# MCU_Signals.net
KiCad netlist of a schematic drawn in Altium Designer
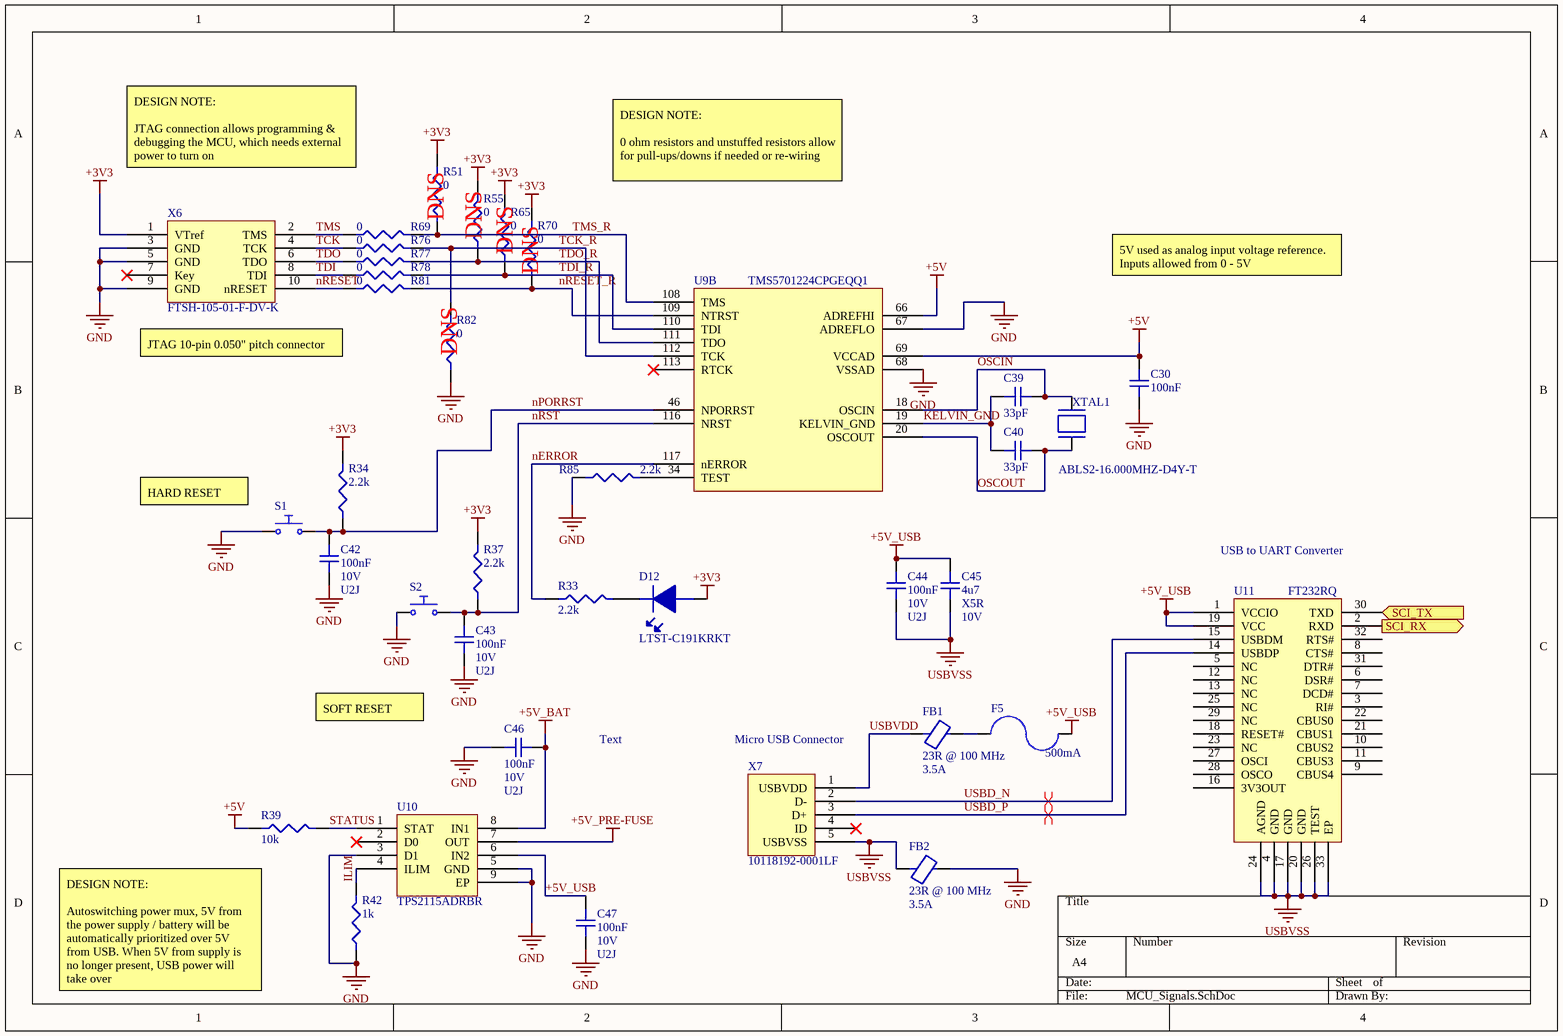
[diagram p0: MCU_Signals.SchDoc]

(export (version "E")
  (design (tool "Eeschema 10.0.6"))
  (components
    (comp (ref "C30")
      (value "100nF")
      (footprint "PHANTOM_FOOTPRINTS:C0805")
      (description "CAP MLCC 100nF 10Volts U2J 5%")
      (fields
        (field (name "MANUFACTURER") "Murata")
        (field (name "MANUFACTURER PART NUMBER") "GRM21B7U1A104JA01L")
      )
      (libsource (lib "PHANTOM_LIBRARY") (part "GRM21B7U1A104JA01L"))
    )
    (comp (ref "C39")
      (value "33pF")
      (footprint "C0805")
      (fields
        (field (name "MANUFACTURER") "Wurth Electronics")
        (field (name "MANUFACTURER PART NUMBER") "885012007003")
        (field (name "TOLERANCE") "5%")
      )
      (libsource (lib "PHANTOM_LIBRARY") (part "885012007003"))
    )
    (comp (ref "C40")
      (value "33pF")
      (footprint "C0805")
      (fields
        (field (name "MANUFACTURER") "Wurth Electronics")
        (field (name "MANUFACTURER PART NUMBER") "885012007003")
        (field (name "TOLERANCE") "5%")
      )
      (libsource (lib "PHANTOM_LIBRARY") (part "885012007003"))
    )
    (comp (ref "C42")
      (value "100nF")
      (footprint "PHANTOM_FOOTPRINTS:C0805")
      (description "CAP MLCC 100nF 10Volts U2J 5%")
      (fields
        (field (name "MANUFACTURER") "Murata")
        (field (name "MANUFACTURER PART NUMBER") "GRM21B7U1A104JA01L")
        (field (name "VOLTAGE RATING") "10V")
        (field (name "DIELECTRIC") "U2J")
      )
      (libsource (lib "PHANTOM_LIBRARY") (part "GRM21B7U1A104JA01L"))
    )
    (comp (ref "C43")
      (value "100nF")
      (footprint "PHANTOM_FOOTPRINTS:C0805")
      (description "CAP MLCC 100nF 10Volts U2J 5%")
      (fields
        (field (name "MANUFACTURER") "Murata")
        (field (name "MANUFACTURER PART NUMBER") "GRM21B7U1A104JA01L")
        (field (name "VOLTAGE RATING") "10V")
        (field (name "DIELECTRIC") "U2J")
      )
      (libsource (lib "PHANTOM_LIBRARY") (part "GRM21B7U1A104JA01L"))
    )
    (comp (ref "C44")
      (value "100nF")
      (footprint "PHANTOM_FOOTPRINTS:C0805")
      (description "CAP MLCC 100nF 10Volts U2J 5%")
      (fields
        (field (name "MANUFACTURER") "Murata")
        (field (name "MANUFACTURER PART NUMBER") "GRM21B7U1A104JA01L")
        (field (name "VOLTAGE RATING") "10V")
        (field (name "DIELECTRIC") "U2J")
      )
      (libsource (lib "PHANTOM_LIBRARY") (part "GRM21B7U1A104JA01L"))
    )
    (comp (ref "C45")
      (value "4u7")
      (footprint "C0805")
      (fields
        (field (name "MANUFACTURER") "Murata")
        (field (name "MANUFACTURER PART NUMBER") "GRM219R61A475KE34D")
        (field (name "TOLERANCE") "10%")
        (field (name "DIELECTRIC") "X5R")
        (field (name "VOLTAGE") "10V")
      )
      (libsource (lib "PHANTOM_LIBRARY") (part "GRM219R61A475KE34D"))
    )
    (comp (ref "C46")
      (value "100nF")
      (footprint "PHANTOM_FOOTPRINTS:C0805")
      (description "CAP MLCC 100nF 10Volts U2J 5%")
      (fields
        (field (name "MANUFACTURER") "Murata")
        (field (name "MANUFACTURER PART NUMBER") "GRM21B7U1A104JA01L")
        (field (name "VOLTAGE RATING") "10V")
        (field (name "DIELECTRIC") "U2J")
      )
      (libsource (lib "PHANTOM_LIBRARY") (part "GRM21B7U1A104JA01L"))
    )
    (comp (ref "C47")
      (value "100nF")
      (footprint "PHANTOM_FOOTPRINTS:C0805")
      (description "CAP MLCC 100nF 10Volts U2J 5%")
      (fields
        (field (name "MANUFACTURER") "Murata")
        (field (name "MANUFACTURER PART NUMBER") "GRM21B7U1A104JA01L")
        (field (name "VOLTAGE RATING") "10V")
        (field (name "DIELECTRIC") "U2J")
      )
      (libsource (lib "PHANTOM_LIBRARY") (part "GRM21B7U1A104JA01L"))
    )
    (comp (ref "D12")
      (value "LTST-C191KRKT")
      (footprint "LED_0603")
      (description "LED RED CLEAR 0603 SMD")
      (fields (field (name "MANUFACTURER") "Vishay Lite-On") (field (name "VOLTAGE") "2V"))
      (libsource (lib "PHANTOM_LIBRARY") (part "LTST-C191KRKT"))
    )
    (comp (ref "F5")
      (value "500mA")
      (footprint "FUSE_0603")
      (description "FUSE_0.5A SMD 0603, 0.5A")
      (fields
        (field (name "MANUFACTURER") "Panasonic ECG")
        (field (name "MANUFACTURER PART NUMBER") "ERB-RE0R50V")
      )
      (libsource (lib "PHANTOM_LIBRARY") (part "ERB-RE0R50V"))
    )
    (comp (ref "FB1")
      (value "23R @ 100 MHz")
      (footprint "FB_1806")
      (description "FERRITE BEAD Ind Chip Bead Multi-Layer 23Ohm 30% 100MHz Ferrite 3.5A 1806 T/R")
      (fields
        (field (name "MANUFACTURER") "Taiyo Yuden")
        (field (name "MANUFACTURER PART NUMBER") "FBMJ4516HL230NTV")
        (field (name "MAX CURRENT RATING") "3.5A")
      )
      (libsource (lib "PHANTOM_LIBRARY") (part "FBMJ4516HL230NTV"))
    )
    (comp (ref "FB2")
      (value "23R @ 100 MHz")
      (footprint "FB_1806")
      (description "FERRITE BEAD Ind Chip Bead Multi-Layer 23Ohm 30% 100MHz Ferrite 3.5A 1806 T/R")
      (fields
        (field (name "MANUFACTURER") "Taiyo Yuden")
        (field (name "MANUFACTURER PART NUMBER") "FBMJ4516HL230NTV")
        (field (name "MAX CURRENT RATING") "3.5A")
      )
      (libsource (lib "PHANTOM_LIBRARY") (part "FBMJ4516HL230NTV"))
    )
    (comp (ref "R33")
      (value "2.2k")
      (footprint "R0805")
      (description "RES SMD 2.2K OHM 5% 1/8W")
      (fields
        (field (name "MANUFACTURER") "Yageo")
        (field (name "MANUFACTURER PART NUMBER") "RC0805JR-072K2L")
      )
      (libsource (lib "PHANTOM_LIBRARY") (part "RC0805JR-072K2L"))
    )
    (comp (ref "R34")
      (value "2.2k")
      (footprint "R0805")
      (description "RES SMD 2.2K OHM 5% 1/8W")
      (fields
        (field (name "MANUFACTURER") "Yageo")
        (field (name "MANUFACTURER PART NUMBER") "RC0805JR-072K2L")
      )
      (libsource (lib "PHANTOM_LIBRARY") (part "RC0805JR-072K2L"))
    )
    (comp (ref "R37")
      (value "2.2k")
      (footprint "R0805")
      (description "RES SMD 2.2K OHM 5% 1/8W")
      (fields
        (field (name "MANUFACTURER") "Yageo")
        (field (name "MANUFACTURER PART NUMBER") "RC0805JR-072K2L")
      )
      (libsource (lib "PHANTOM_LIBRARY") (part "RC0805JR-072K2L"))
    )
    (comp (ref "R39")
      (value "10k")
      (footprint "R0805")
      (description "RES SMD 10K OHM 1% 1/8W 0805")
      (fields
        (field (name "MANUFACTURER") "Yageo Phycomp")
        (field (name "MANUFACTURER PART NUMBER") "RC0805FR-071KL")
      )
      (libsource (lib "PHANTOM_LIBRARY") (part "RC0805FR-071KL"))
    )
    (comp (ref "R42")
      (value "1k")
      (footprint "R0805")
      (description "RES SMD 1K OHM 0805 1K Ohm 0.1% 0.125W(1/8W) ±25ppm/C Molded SMD Automotive Punched T/R")
      (fields
        (field (name "MANUFACTURER") "Panasonic ECG")
        (field (name "MANUFACTURER PART NUMBER") "ERA-6AEB102V")
      )
      (libsource (lib "PHANTOM_LIBRARY") (part "ERA-6AEB102V"))
    )
    (comp (ref "R51")
      (value "0")
      (footprint "R0805")
      (description "RES SMD 0 OHM 1/8W 0805")
      (fields
        (field (name "MANUFACTURER") "Yageo")
        (field (name "MANUFACTURER PART NUMBER") "RC0805JR-070RL")
      )
      (libsource (lib "PHANTOM_LIBRARY") (part "RC0805JR-070RL"))
    )
    (comp (ref "R55")
      (value "0")
      (footprint "R0805")
      (description "RES SMD 0 OHM 1/8W 0805")
      (fields
        (field (name "MANUFACTURER") "Yageo")
        (field (name "MANUFACTURER PART NUMBER") "RC0805JR-070RL")
      )
      (libsource (lib "PHANTOM_LIBRARY") (part "RC0805JR-070RL"))
    )
    (comp (ref "R65")
      (value "0")
      (footprint "R0805")
      (description "RES SMD 0 OHM 1/8W 0805")
      (fields
        (field (name "MANUFACTURER") "Yageo")
        (field (name "MANUFACTURER PART NUMBER") "RC0805JR-070RL")
      )
      (libsource (lib "PHANTOM_LIBRARY") (part "RC0805JR-070RL"))
    )
    (comp (ref "R69")
      (value "0")
      (footprint "R0805")
      (description "RES SMD 0 OHM 1/8W 0805")
      (fields
        (field (name "MANUFACTURER") "Yageo")
        (field (name "MANUFACTURER PART NUMBER") "RC0805JR-070RL")
      )
      (libsource (lib "PHANTOM_LIBRARY") (part "RC0805JR-070RL"))
    )
    (comp (ref "R70")
      (value "0")
      (footprint "R0805")
      (description "RES SMD 0 OHM 1/8W 0805")
      (fields
        (field (name "MANUFACTURER") "Yageo")
        (field (name "MANUFACTURER PART NUMBER") "RC0805JR-070RL")
      )
      (libsource (lib "PHANTOM_LIBRARY") (part "RC0805JR-070RL"))
    )
    (comp (ref "R76")
      (value "0")
      (footprint "R0805")
      (description "RES SMD 0 OHM 1/8W 0805")
      (fields
        (field (name "MANUFACTURER") "Yageo")
        (field (name "MANUFACTURER PART NUMBER") "RC0805JR-070RL")
      )
      (libsource (lib "PHANTOM_LIBRARY") (part "RC0805JR-070RL"))
    )
    (comp (ref "R77")
      (value "0")
      (footprint "R0805")
      (description "RES SMD 0 OHM 1/8W 0805")
      (fields
        (field (name "MANUFACTURER") "Yageo")
        (field (name "MANUFACTURER PART NUMBER") "RC0805JR-070RL")
      )
      (libsource (lib "PHANTOM_LIBRARY") (part "RC0805JR-070RL"))
    )
    (comp (ref "R78")
      (value "0")
      (footprint "R0805")
      (description "RES SMD 0 OHM 1/8W 0805")
      (fields
        (field (name "MANUFACTURER") "Yageo")
        (field (name "MANUFACTURER PART NUMBER") "RC0805JR-070RL")
      )
      (libsource (lib "PHANTOM_LIBRARY") (part "RC0805JR-070RL"))
    )
    (comp (ref "R81")
      (value "0")
      (footprint "R0805")
      (description "RES SMD 0 OHM 1/8W 0805")
      (fields
        (field (name "MANUFACTURER") "Yageo")
        (field (name "MANUFACTURER PART NUMBER") "RC0805JR-070RL")
      )
      (libsource (lib "PHANTOM_LIBRARY") (part "RC0805JR-070RL"))
    )
    (comp (ref "R82")
      (value "0")
      (footprint "R0805")
      (description "RES SMD 0 OHM 1/8W 0805")
      (fields
        (field (name "MANUFACTURER") "Yageo")
        (field (name "MANUFACTURER PART NUMBER") "RC0805JR-070RL")
      )
      (libsource (lib "PHANTOM_LIBRARY") (part "RC0805JR-070RL"))
    )
    (comp (ref "R85")
      (value "2.2k")
      (footprint "R0805")
      (description "RES SMD 2.2K OHM 5% 1/8W")
      (fields
        (field (name "MANUFACTURER") "Yageo")
        (field (name "MANUFACTURER PART NUMBER") "RC0805JR-072K2L")
      )
      (libsource (lib "PHANTOM_LIBRARY") (part "RC0805JR-072K2L"))
    )
    (comp (ref "S1")
      (value "PTS645SM43SMTR92LFS")
      (footprint "PUSH_BUTTON")
      (description "SWITCH TACTILE SPST-NO 0.05A 12V")
      (fields (field (name "MANUFACTURER") "ITT C&K"))
      (libsource (lib "PHANTOM_LIBRARY") (part "PTS645SM43SMTR92LFS"))
    )
    (comp (ref "S2")
      (value "PTS645SM43SMTR92LFS")
      (footprint "PUSH_BUTTON")
      (description "SWITCH TACTILE SPST-NO 0.05A 12V")
      (fields (field (name "MANUFACTURER") "ITT C&K"))
      (libsource (lib "PHANTOM_LIBRARY") (part "PTS645SM43SMTR92LFS"))
    )
    (comp (ref "U9")
      (value "TMS5701224CPGEQQ1")
      (footprint "LQFP-144")
      (description "ARM CORTEX R4 LOCK STEP HERCULES MCU")
      (fields (field (name "MANUFACTURER") "Texas Instruments"))
      (libsource (lib "PHANTOM_LIBRARY") (part "TMS5701224CPGEQQ1"))
    )
    (comp (ref "U10")
      (value "TPS2115ADRBR")
      (footprint "VSON-8")
      (description "IC OR CTRLR SRC SELECT 8SON")
      (fields (field (name "MANUFACTURER") "Texas Instruments"))
      (libsource (lib "PHANTOM_LIBRARY") (part "TPS2115ADRBR"))
    )
    (comp (ref "U11")
      (value "FT232RQ")
      (footprint "QFN-32")
      (description "IC USB FS SERIAL UART 32-QFN")
      (fields (field (name "MANUFACTURER") "FTDI") (field (name "MANUFACTURER PART NUMBER") "FT232RQ-REEL"))
      (libsource (lib "PHANTOM_LIBRARY") (part "FT232RQ-REEL"))
    )
    (comp (ref "X6")
      (value "FTSH-105-01-F-DV-K")
      (footprint "JTAG_50mil_10pin")
      (description "CONN_JTAG_10pin .050 Connector Dual Header 10 Position Surface Mount")
      (fields (field (name "MANUFACTURER") "Samtec"))
      (libsource (lib "PHANTOM_LIBRARY") (part "FTSH-105-01-F-DV-K"))
    )
    (comp (ref "X7")
      (value "10118192-0001LF")
      (footprint "USB_MICRO")
      (description "CONN_USB - micro B USB 2.0 Receptacle Connector 5 Position Surface Mount, Right Angle, Horizontal")
      (fields (field (name "MANUFACTURER") "Amphenol FCI"))
      (libsource (lib "PHANTOM_LIBRARY") (part "10118192-0001LF"))
    )
    (comp (ref "XTAL1")
      (value "ABLS2-16.000MHZ-D4Y-T")
      (footprint "XTAL")
      (description "XTAL 16MHz ±30ppm Crystal 18pF 40 Ohm -40°C ~ 85°C  Surface Mount HC49/US")
      (fields (field (name "MANUFACTURER") "Abracon") (field (name "TOLERANCE") "30ppm"))
      (libsource (lib "PHANTOM_LIBRARY") (part "ABLS2-16.000MHZ-D4Y-T"))
    )
  )
  (nets
    (net (code "1") (name "+3V3") (class "Default")
      (node (ref "D12") (pin "1") (pinfunction "1_1") (pintype "passive"))
      (node (ref "R34") (pin "2") (pinfunction "2_2") (pintype "passive"))
      (node (ref "R37") (pin "2") (pinfunction "2_2") (pintype "passive"))
      (node (ref "R51") (pin "2") (pinfunction "2_2") (pintype "passive"))
      (node (ref "R55") (pin "2") (pinfunction "2_2") (pintype "passive"))
      (node (ref "R65") (pin "2") (pinfunction "2_2") (pintype "passive"))
      (node (ref "R70") (pin "2") (pinfunction "2_2") (pintype "passive"))
      (node (ref "X6") (pin "1") (pinfunction "VTref_1") (pintype "passive"))
    )
    (net (code "2") (name "+5V") (class "Default")
      (node (ref "C30") (pin "2") (pinfunction "2_2") (pintype "passive"))
      (node (ref "R39") (pin "1") (pinfunction "1_1") (pintype "passive"))
      (node (ref "U9") (pin "66") (pinfunction "ADREFHI_66") (pintype "passive"))
      (node (ref "U9") (pin "69") (pinfunction "VCCAD_69") (pintype "passive"))
    )
    (net (code "3") (name "+5V_BAT") (class "Default")
      (node (ref "C46") (pin "2") (pinfunction "2_2") (pintype "passive"))
      (node (ref "U10") (pin "8") (pinfunction "IN1_8") (pintype "passive"))
    )
    (net (code "4") (name "+5V_PRE-FUSE") (class "Default")
      (node (ref "U10") (pin "7") (pinfunction "OUT_7") (pintype "passive"))
    )
    (net (code "5") (name "+5V_USB") (class "Default")
      (node (ref "C44") (pin "2") (pinfunction "2_2") (pintype "passive"))
      (node (ref "C45") (pin "2") (pinfunction "2_2") (pintype "passive"))
      (node (ref "C47") (pin "1") (pinfunction "1_1") (pintype "passive"))
      (node (ref "F5") (pin "2") (pinfunction "2_2") (pintype "passive"))
      (node (ref "U10") (pin "6") (pinfunction "IN2_6") (pintype "passive"))
      (node (ref "U11") (pin "1") (pinfunction "VCCIO_1") (pintype "passive"))
      (node (ref "U11") (pin "19") (pinfunction "VCC_19") (pintype "passive"))
    )
    (net (code "6") (name "/ILIM") (class "Default")
      (node (ref "R42") (pin "2") (pinfunction "2_2") (pintype "passive"))
      (node (ref "U10") (pin "4") (pinfunction "ILIM_4") (pintype "passive"))
    )
    (net (code "7") (name "/KELVIN_GND") (class "Default")
      (node (ref "C39") (pin "1") (pinfunction "1_1") (pintype "passive"))
      (node (ref "C40") (pin "1") (pinfunction "1_1") (pintype "passive"))
      (node (ref "U9") (pin "19") (pinfunction "KELVIN_GND_19") (pintype "passive"))
    )
    (net (code "8") (name "/OSCIN") (class "Default")
      (node (ref "C39") (pin "2") (pinfunction "2_2") (pintype "passive"))
      (node (ref "U9") (pin "18") (pinfunction "OSCIN_18") (pintype "passive"))
      (node (ref "XTAL1") (pin "1") (pintype "passive"))
    )
    (net (code "9") (name "/OSCOUT") (class "Default")
      (node (ref "C40") (pin "2") (pinfunction "2_2") (pintype "passive"))
      (node (ref "U9") (pin "20") (pinfunction "OSCOUT_20") (pintype "passive"))
      (node (ref "XTAL1") (pin "2") (pintype "passive"))
    )
    (net (code "10") (name "/SCI_RX") (class "Default")
      (node (ref "U11") (pin "2") (pinfunction "RXD_2") (pintype "passive"))
    )
    (net (code "11") (name "/SCI_TX") (class "Default")
      (node (ref "U11") (pin "30") (pinfunction "TXD_30") (pintype "passive"))
    )
    (net (code "12") (name "/STATUS") (class "Default")
      (node (ref "R39") (pin "2") (pinfunction "2_2") (pintype "passive"))
      (node (ref "U10") (pin "1") (pinfunction "STAT_1") (pintype "passive"))
    )
    (net (code "13") (name "/TCK") (class "Default")
      (node (ref "R76") (pin "1") (pinfunction "1_1") (pintype "passive"))
      (node (ref "X6") (pin "4") (pinfunction "TCK_4") (pintype "passive"))
    )
    (net (code "14") (name "/TCK_R") (class "Default")
      (node (ref "R76") (pin "2") (pinfunction "2_2") (pintype "passive"))
      (node (ref "R82") (pin "2") (pinfunction "2_2") (pintype "passive"))
      (node (ref "U9") (pin "112") (pinfunction "TCK_112") (pintype "passive"))
    )
    (net (code "15") (name "/TDI") (class "Default")
      (node (ref "R78") (pin "1") (pinfunction "1_1") (pintype "passive"))
      (node (ref "X6") (pin "8") (pinfunction "TDI_8") (pintype "passive"))
    )
    (net (code "16") (name "/TDI_R") (class "Default")
      (node (ref "R65") (pin "1") (pinfunction "1_1") (pintype "passive"))
      (node (ref "R78") (pin "2") (pinfunction "2_2") (pintype "passive"))
      (node (ref "U9") (pin "110") (pinfunction "TDI_110") (pintype "passive"))
    )
    (net (code "17") (name "/TDO") (class "Default")
      (node (ref "R77") (pin "1") (pinfunction "1_1") (pintype "passive"))
      (node (ref "X6") (pin "6") (pinfunction "TDO_6") (pintype "passive"))
    )
    (net (code "18") (name "/TDO_R") (class "Default")
      (node (ref "R55") (pin "1") (pinfunction "1_1") (pintype "passive"))
      (node (ref "R77") (pin "2") (pinfunction "2_2") (pintype "passive"))
      (node (ref "U9") (pin "111") (pinfunction "TDO_111") (pintype "passive"))
    )
    (net (code "19") (name "/TMS") (class "Default")
      (node (ref "R69") (pin "1") (pinfunction "1_1") (pintype "passive"))
      (node (ref "X6") (pin "2") (pinfunction "TMS_2") (pintype "passive"))
    )
    (net (code "20") (name "/TMS_R") (class "Default")
      (node (ref "R51") (pin "1") (pinfunction "1_1") (pintype "passive"))
      (node (ref "R69") (pin "2") (pinfunction "2_2") (pintype "passive"))
      (node (ref "U9") (pin "108") (pinfunction "TMS_108") (pintype "passive"))
    )
    (net (code "21") (name "/USBD_N") (class "Default")
      (node (ref "U11") (pin "15") (pinfunction "USBDM_15") (pintype "passive"))
      (node (ref "X7") (pin "2") (pinfunction "D-_2") (pintype "passive"))
    )
    (net (code "22") (name "/USBD_P") (class "Default")
      (node (ref "U11") (pin "14") (pinfunction "USBDP_14") (pintype "passive"))
      (node (ref "X7") (pin "3") (pinfunction "D+_3") (pintype "passive"))
    )
    (net (code "23") (name "/USBVDD") (class "Default")
      (node (ref "FB1") (pin "1") (pinfunction "1_1") (pintype "passive"))
      (node (ref "X7") (pin "1") (pinfunction "USBVDD_1") (pintype "passive"))
    )
    (net (code "24") (name "/nERROR") (class "Default")
      (node (ref "R33") (pin "1") (pinfunction "1_1") (pintype "passive"))
      (node (ref "U9") (pin "117") (pinfunction "nERROR_117") (pintype "passive"))
    )
    (net (code "25") (name "/nPORRST") (class "Default")
      (node (ref "C42") (pin "2") (pinfunction "2_2") (pintype "passive"))
      (node (ref "R34") (pin "1") (pinfunction "1_1") (pintype "passive"))
      (node (ref "S1") (pin "2") (pinfunction "2_2") (pintype "passive"))
      (node (ref "U9") (pin "46") (pinfunction "NPORRST_46") (pintype "passive"))
    )
    (net (code "26") (name "/nRESET") (class "Default")
      (node (ref "R81") (pin "1") (pinfunction "1_1") (pintype "passive"))
      (node (ref "X6") (pin "10") (pinfunction "nRESET_10") (pintype "passive"))
    )
    (net (code "27") (name "/nRESET_R") (class "Default")
      (node (ref "R70") (pin "1") (pinfunction "1_1") (pintype "passive"))
      (node (ref "R81") (pin "2") (pinfunction "2_2") (pintype "passive"))
      (node (ref "U9") (pin "109") (pinfunction "NTRST_109") (pintype "passive"))
    )
    (net (code "28") (name "/nRST") (class "Default")
      (node (ref "C43") (pin "2") (pinfunction "2_2") (pintype "passive"))
      (node (ref "R37") (pin "1") (pinfunction "1_1") (pintype "passive"))
      (node (ref "S2") (pin "2") (pinfunction "2_2") (pintype "passive"))
      (node (ref "U9") (pin "116") (pinfunction "NRST_116") (pintype "passive"))
    )
    (net (code "29") (name "GND") (class "Default")
      (node (ref "C30") (pin "1") (pinfunction "1_1") (pintype "passive"))
      (node (ref "C42") (pin "1") (pinfunction "1_1") (pintype "passive"))
      (node (ref "C43") (pin "1") (pinfunction "1_1") (pintype "passive"))
      (node (ref "C46") (pin "1") (pinfunction "1_1") (pintype "passive"))
      (node (ref "C47") (pin "2") (pinfunction "2_2") (pintype "passive"))
      (node (ref "FB2") (pin "2") (pinfunction "2_2") (pintype "passive"))
      (node (ref "R42") (pin "1") (pinfunction "1_1") (pintype "passive"))
      (node (ref "R82") (pin "1") (pinfunction "1_1") (pintype "passive"))
      (node (ref "R85") (pin "1") (pinfunction "1_1") (pintype "passive"))
      (node (ref "S1") (pin "1") (pinfunction "1_1") (pintype "passive"))
      (node (ref "S2") (pin "1") (pinfunction "1_1") (pintype "passive"))
      (node (ref "U10") (pin "3") (pinfunction "D1_3") (pintype "passive"))
      (node (ref "U10") (pin "5") (pinfunction "GND_5") (pintype "passive"))
      (node (ref "U10") (pin "9") (pinfunction "EP_9") (pintype "passive"))
      (node (ref "U9") (pin "67") (pinfunction "ADREFLO_67") (pintype "passive"))
      (node (ref "U9") (pin "68") (pinfunction "VSSAD_68") (pintype "passive"))
      (node (ref "X6") (pin "3") (pinfunction "GND_3") (pintype "passive"))
      (node (ref "X6") (pin "5") (pinfunction "GND_5") (pintype "passive"))
      (node (ref "X6") (pin "9") (pinfunction "GND_9") (pintype "passive"))
    )
    (net (code "30") (name "Net-(D12-Pad2)") (class "Default")
      (node (ref "D12") (pin "2") (pinfunction "2_2") (pintype "passive"))
      (node (ref "R33") (pin "2") (pinfunction "2_2") (pintype "passive"))
    )
    (net (code "31") (name "Net-(F5-Pad1)") (class "Default")
      (node (ref "F5") (pin "1") (pinfunction "1_1") (pintype "passive"))
      (node (ref "FB1") (pin "2") (pinfunction "2_2") (pintype "passive"))
    )
    (net (code "32") (name "Net-(U9B-TEST)") (class "Default")
      (node (ref "R85") (pin "2") (pinfunction "2_2") (pintype "passive"))
      (node (ref "U9") (pin "34") (pinfunction "TEST_34") (pintype "passive"))
    )
    (net (code "33") (name "USBVSS") (class "Default")
      (node (ref "C44") (pin "1") (pinfunction "1_1") (pintype "passive"))
      (node (ref "C45") (pin "1") (pinfunction "1_1") (pintype "passive"))
      (node (ref "FB2") (pin "1") (pinfunction "1_1") (pintype "passive"))
      (node (ref "U11") (pin "17") (pinfunction "GND_17") (pintype "passive"))
      (node (ref "U11") (pin "20") (pinfunction "GND_20") (pintype "passive"))
      (node (ref "U11") (pin "24") (pinfunction "AGND_24") (pintype "passive"))
      (node (ref "U11") (pin "26") (pinfunction "TEST_26") (pintype "passive"))
      (node (ref "U11") (pin "33") (pinfunction "EP_33") (pintype "passive"))
      (node (ref "U11") (pin "4") (pinfunction "GND_4") (pintype "passive"))
      (node (ref "X7") (pin "5") (pinfunction "USBVSS_5") (pintype "passive"))
    )
    (net (code "34") (name "unconnected-(U9B-RTCK-Pad113)") (class "Default")
      (node (ref "U9") (pin "113") (pinfunction "RTCK_113") (pintype "passive+no_connect"))
    )
    (net (code "35") (name "unconnected-(U10-D0-Pad2)") (class "Default")
      (node (ref "U10") (pin "2") (pinfunction "D0_2") (pintype "passive+no_connect"))
    )
    (net (code "36") (name "unconnected-(U11-3V3OUT-Pad16)") (class "Default")
      (node (ref "U11") (pin "16") (pinfunction "3V3OUT_16") (pintype "passive"))
    )
    (net (code "37") (name "unconnected-(U11-CBUS0-Pad22)") (class "Default")
      (node (ref "U11") (pin "22") (pinfunction "CBUS0_22") (pintype "passive"))
    )
    (net (code "38") (name "unconnected-(U11-CBUS1-Pad21)") (class "Default")
      (node (ref "U11") (pin "21") (pinfunction "CBUS1_21") (pintype "passive"))
    )
    (net (code "39") (name "unconnected-(U11-CBUS2-Pad10)") (class "Default")
      (node (ref "U11") (pin "10") (pinfunction "CBUS2_10") (pintype "passive"))
    )
    (net (code "40") (name "unconnected-(U11-CBUS3-Pad11)") (class "Default")
      (node (ref "U11") (pin "11") (pinfunction "CBUS3_11") (pintype "passive"))
    )
    (net (code "41") (name "unconnected-(U11-CBUS4-Pad9)") (class "Default")
      (node (ref "U11") (pin "9") (pinfunction "CBUS4_9") (pintype "passive"))
    )
    (net (code "42") (name "unconnected-(U11-CTS#-Pad8)") (class "Default")
      (node (ref "U11") (pin "8") (pinfunction "CTS#_8") (pintype "passive"))
    )
    (net (code "43") (name "unconnected-(U11-DCD#-Pad7)") (class "Default")
      (node (ref "U11") (pin "7") (pinfunction "DCD#_7") (pintype "passive"))
    )
    (net (code "44") (name "unconnected-(U11-DSR#-Pad6)") (class "Default")
      (node (ref "U11") (pin "6") (pinfunction "DSR#_6") (pintype "passive"))
    )
    (net (code "45") (name "unconnected-(U11-DTR#-Pad31)") (class "Default")
      (node (ref "U11") (pin "31") (pinfunction "DTR#_31") (pintype "passive"))
    )
    (net (code "46") (name "unconnected-(U11-NC-Pad5)") (class "Default")
      (node (ref "U11") (pin "5") (pinfunction "NC_5") (pintype "passive"))
    )
    (net (code "47") (name "unconnected-(U11-NC-Pad12)") (class "Default")
      (node (ref "U11") (pin "12") (pinfunction "NC_12") (pintype "passive"))
    )
    (net (code "48") (name "unconnected-(U11-NC-Pad13)") (class "Default")
      (node (ref "U11") (pin "13") (pinfunction "NC_13") (pintype "passive"))
    )
    (net (code "49") (name "unconnected-(U11-NC-Pad23)") (class "Default")
      (node (ref "U11") (pin "23") (pinfunction "NC_23") (pintype "passive"))
    )
    (net (code "50") (name "unconnected-(U11-NC-Pad25)") (class "Default")
      (node (ref "U11") (pin "25") (pinfunction "NC_25") (pintype "passive"))
    )
    (net (code "51") (name "unconnected-(U11-NC-Pad29)") (class "Default")
      (node (ref "U11") (pin "29") (pinfunction "NC_29") (pintype "passive"))
    )
    (net (code "52") (name "unconnected-(U11-OSCI-Pad27)") (class "Default")
      (node (ref "U11") (pin "27") (pinfunction "OSCI_27") (pintype "passive"))
    )
    (net (code "53") (name "unconnected-(U11-OSCO-Pad28)") (class "Default")
      (node (ref "U11") (pin "28") (pinfunction "OSCO_28") (pintype "passive"))
    )
    (net (code "54") (name "unconnected-(U11-RESET#-Pad18)") (class "Default")
      (node (ref "U11") (pin "18") (pinfunction "RESET#_18") (pintype "passive"))
    )
    (net (code "55") (name "unconnected-(U11-RI#-Pad3)") (class "Default")
      (node (ref "U11") (pin "3") (pinfunction "RI#_3") (pintype "passive"))
    )
    (net (code "56") (name "unconnected-(U11-RTS#-Pad32)") (class "Default")
      (node (ref "U11") (pin "32") (pinfunction "RTS#_32") (pintype "passive"))
    )
    (net (code "57") (name "unconnected-(X6-Key-Pad7)") (class "Default")
      (node (ref "X6") (pin "7") (pinfunction "Key_7") (pintype "passive+no_connect"))
    )
    (net (code "58") (name "unconnected-(X7-ID-Pad4)") (class "Default")
      (node (ref "X7") (pin "4") (pinfunction "ID_4") (pintype "passive+no_connect"))
    )
  )
)
